# DEBUG.net
KiCad netlist of a schematic drawn in Altium Designer
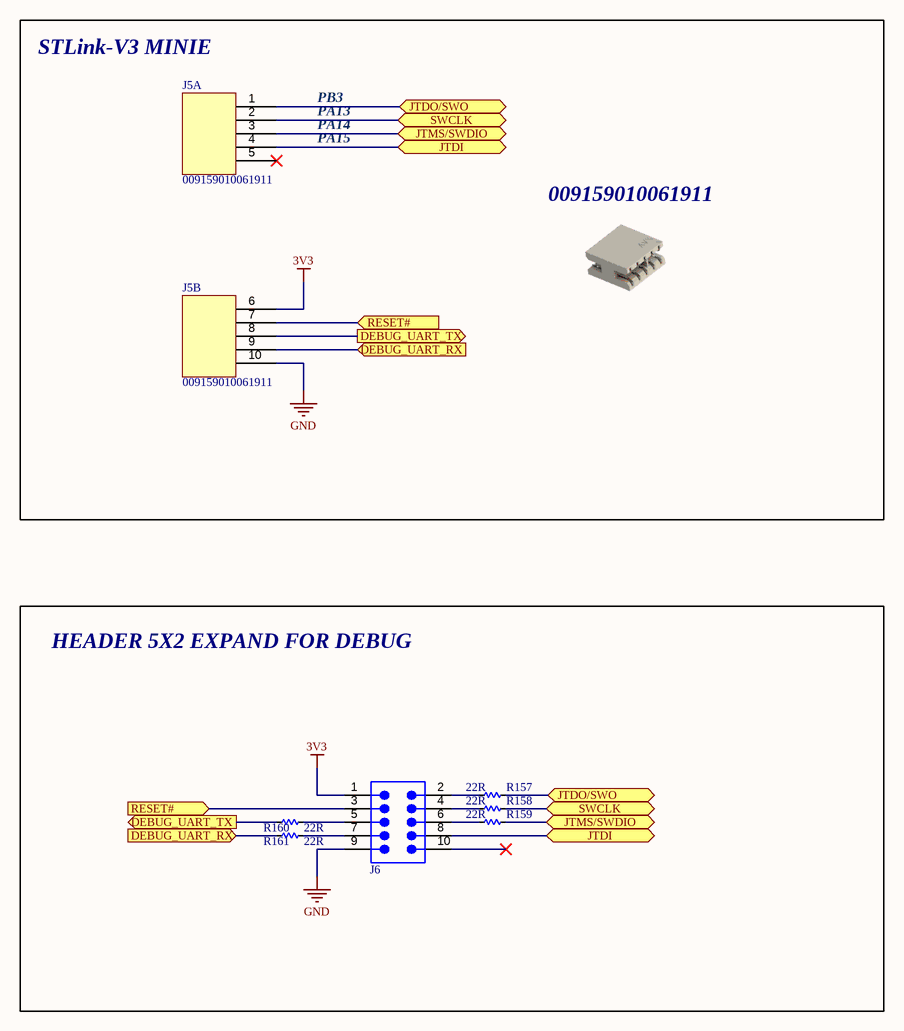
[diagram p0: DEBUG.SchDoc]

(export (version "E")
  (design (tool "Eeschema 10.0.6"))
  (components
    (comp (ref "J5")
      (value "009159010061911")
      (footprint "009159010061911")
      (description "pads for STLink V3 minie")
      (libsource (lib "COMM_SCHLIB") (part "009159010061911"))
    )
    (comp (ref "J6")
      (value "61301021121")
      (footprint "61301021121")
      (description "WR-PHD Pin Header, THT, Vertical, pitch 2.54mm, 2 Row, 10P")
      (fields (field (name "MANUFACTURER") "Wurth Elektronik"))
      (libsource (lib "COMM_SCHLIB") (part "61301021121"))
    )
    (comp (ref "R157")
      (value "22R")
      (footprint "RES_C_1608X60")
      (description "RES")
      (libsource (lib "LABLIB") (part "_RES_B_2"))
    )
    (comp (ref "R158")
      (value "22R")
      (footprint "RES_C_1608X60")
      (description "RES")
      (libsource (lib "LABLIB") (part "_RES_B_2"))
    )
    (comp (ref "R159")
      (value "22R")
      (footprint "RES_C_1608X60")
      (description "RES")
      (libsource (lib "LABLIB") (part "_RES_B_2"))
    )
    (comp (ref "R160")
      (value "22R")
      (footprint "RES_C_1608X60")
      (description "RES")
      (libsource (lib "LABLIB") (part "_RES_B_2"))
    )
    (comp (ref "R161")
      (value "22R")
      (footprint "RES_C_1608X60")
      (description "RES")
      (libsource (lib "LABLIB") (part "_RES_B_2"))
    )
  )
  (nets
    (net (code "1") (name "/DEBUG_UART_RX") (class "Default")
      (node (ref "J5") (pin "9") (pinfunction "9_9") (pintype "passive"))
      (node (ref "R161") (pin "1") (pinfunction "1_1") (pintype "passive"))
    )
    (net (code "2") (name "/DEBUG_UART_TX") (class "Default")
      (node (ref "J5") (pin "8") (pinfunction "8_8") (pintype "passive"))
      (node (ref "R160") (pin "1") (pinfunction "1_1") (pintype "passive"))
    )
    (net (code "3") (name "/JTDI") (class "Default")
      (node (ref "J5") (pin "4") (pintype "passive"))
      (node (ref "J6") (pin "8") (pinfunction "8_8") (pintype "passive"))
    )
    (net (code "4") (name "/JTDO{slash}SWO") (class "Default")
      (node (ref "J5") (pin "1") (pintype "passive"))
      (node (ref "R157") (pin "2") (pinfunction "2_2") (pintype "passive"))
    )
    (net (code "5") (name "/JTMS{slash}SWDIO") (class "Default")
      (node (ref "J5") (pin "3") (pintype "passive"))
      (node (ref "R159") (pin "2") (pinfunction "2_2") (pintype "passive"))
    )
    (net (code "6") (name "/RESET#") (class "Default")
      (node (ref "J5") (pin "7") (pinfunction "7_7") (pintype "passive"))
      (node (ref "J6") (pin "3") (pinfunction "3_3") (pintype "passive"))
    )
    (net (code "7") (name "/SWCLK") (class "Default")
      (node (ref "J5") (pin "2") (pintype "passive"))
      (node (ref "R158") (pin "2") (pinfunction "2_2") (pintype "passive"))
    )
    (net (code "8") (name "3V3") (class "Default")
      (node (ref "J5") (pin "6") (pinfunction "6_6") (pintype "passive"))
      (node (ref "J6") (pin "1") (pinfunction "1_1") (pintype "passive"))
    )
    (net (code "9") (name "GND") (class "Default")
      (node (ref "J5") (pin "10") (pinfunction "10_10") (pintype "passive"))
      (node (ref "J6") (pin "9") (pinfunction "9_9") (pintype "passive"))
    )
    (net (code "10") (name "Net-(J6-Pad2)") (class "Default")
      (node (ref "J6") (pin "2") (pinfunction "2_2") (pintype "passive"))
      (node (ref "R157") (pin "1") (pinfunction "1_1") (pintype "passive"))
    )
    (net (code "11") (name "Net-(J6-Pad4)") (class "Default")
      (node (ref "J6") (pin "4") (pinfunction "4_4") (pintype "passive"))
      (node (ref "R158") (pin "1") (pinfunction "1_1") (pintype "passive"))
    )
    (net (code "12") (name "Net-(J6-Pad5)") (class "Default")
      (node (ref "J6") (pin "5") (pinfunction "5_5") (pintype "passive"))
      (node (ref "R160") (pin "2") (pinfunction "2_2") (pintype "passive"))
    )
    (net (code "13") (name "Net-(J6-Pad6)") (class "Default")
      (node (ref "J6") (pin "6") (pinfunction "6_6") (pintype "passive"))
      (node (ref "R159") (pin "1") (pinfunction "1_1") (pintype "passive"))
    )
    (net (code "14") (name "Net-(J6-Pad7)") (class "Default")
      (node (ref "J6") (pin "7") (pinfunction "7_7") (pintype "passive"))
      (node (ref "R161") (pin "2") (pinfunction "2_2") (pintype "passive"))
    )
    (net (code "15") (name "unconnected-(J5-Pad5)") (class "Default")
      (node (ref "J5") (pin "5") (pinfunction "5_5") (pintype "passive+no_connect"))
    )
    (net (code "16") (name "unconnected-(J6-Pad10)") (class "Default")
      (node (ref "J6") (pin "10") (pinfunction "10_10") (pintype "passive+no_connect"))
    )
  )
)
